# 555timers_with_allmodes.net
KiCad netlist of a schematic drawn in EAGLE
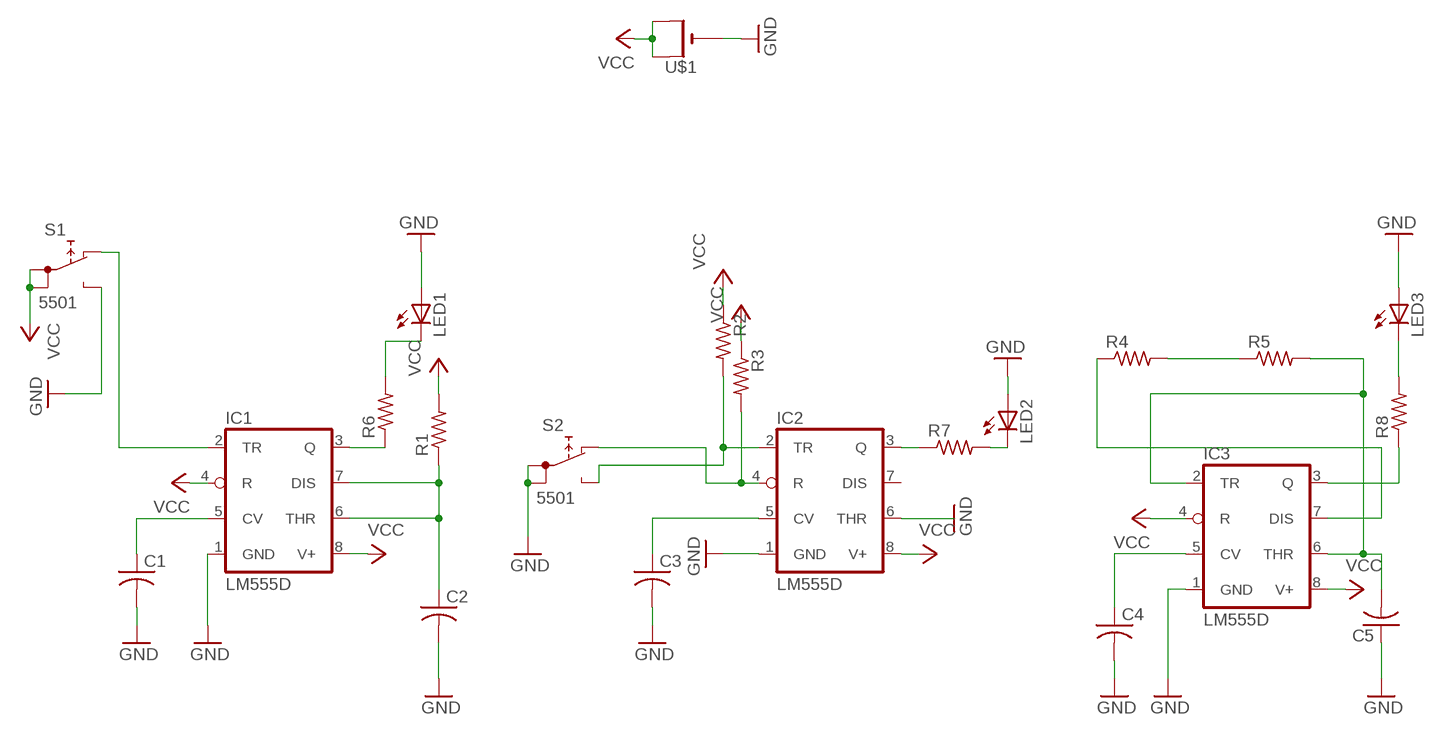
[diagram p0: schematic, sheet 1]

(export (version "E")
  (design (tool "Eeschema 10.0.6"))
  (components
    (comp (ref "C1")
      (value "C-USC0805")
      (footprint "eagle-import:C0805")
      (libsource (lib "eagle-import") (part "C-USC0805"))
    )
    (comp (ref "C2")
      (value "C-USC0805")
      (footprint "eagle-import:C0805")
      (libsource (lib "eagle-import") (part "C-USC0805"))
    )
    (comp (ref "C3")
      (value "C-USC0805")
      (footprint "eagle-import:C0805")
      (libsource (lib "eagle-import") (part "C-USC0805"))
    )
    (comp (ref "C4")
      (value "C-USC0805")
      (footprint "eagle-import:C0805")
      (libsource (lib "eagle-import") (part "C-USC0805"))
    )
    (comp (ref "C5")
      (value "C-USC0805")
      (footprint "eagle-import:C0805")
      (libsource (lib "eagle-import") (part "C-USC0805"))
    )
    (comp (ref "IC1")
      (value "LM555D")
      (footprint "eagle-import:SO08")
      (libsource (lib "eagle-import") (part "555DLM"))
    )
    (comp (ref "IC2")
      (value "LM555D")
      (footprint "eagle-import:SO08")
      (libsource (lib "eagle-import") (part "555DLM"))
    )
    (comp (ref "IC3")
      (value "LM555D")
      (footprint "eagle-import:SO08")
      (libsource (lib "eagle-import") (part "555DLM"))
    )
    (comp (ref "LED1")
      (value "LEDCHIPLED_0805")
      (footprint "eagle-import:CHIPLED_0805")
      (libsource (lib "eagle-import") (part "LEDCHIPLED_0805"))
    )
    (comp (ref "LED2")
      (value "LEDCHIPLED_0805")
      (footprint "eagle-import:CHIPLED_0805")
      (libsource (lib "eagle-import") (part "LEDCHIPLED_0805"))
    )
    (comp (ref "LED3")
      (value "LEDCHIPLED_0805")
      (footprint "eagle-import:CHIPLED_0805")
      (libsource (lib "eagle-import") (part "LEDCHIPLED_0805"))
    )
    (comp (ref "R1")
      (value "R-US_FLIPFLOP")
      (footprint "eagle-import:0805-THM")
      (libsource (lib "eagle-import") (part "R-US_FLIPFLOP"))
    )
    (comp (ref "R2")
      (value "R-US_FLIPFLOP")
      (footprint "eagle-import:0805-THM")
      (libsource (lib "eagle-import") (part "R-US_FLIPFLOP"))
    )
    (comp (ref "R3")
      (value "R-US_FLIPFLOP")
      (footprint "eagle-import:0805-THM")
      (libsource (lib "eagle-import") (part "R-US_FLIPFLOP"))
    )
    (comp (ref "R4")
      (value "R-US_FLIPFLOP")
      (footprint "eagle-import:0805-THM")
      (libsource (lib "eagle-import") (part "R-US_FLIPFLOP"))
    )
    (comp (ref "R5")
      (value "R-US_FLIPFLOP")
      (footprint "eagle-import:0805-THM")
      (libsource (lib "eagle-import") (part "R-US_FLIPFLOP"))
    )
    (comp (ref "R6")
      (value "R-US_FLIPFLOP")
      (footprint "eagle-import:0805-THM")
      (libsource (lib "eagle-import") (part "R-US_FLIPFLOP"))
    )
    (comp (ref "R7")
      (value "R-US_FLIPFLOP")
      (footprint "eagle-import:0805-THM")
      (libsource (lib "eagle-import") (part "R-US_FLIPFLOP"))
    )
    (comp (ref "R8")
      (value "R-US_FLIPFLOP")
      (footprint "eagle-import:0805-THM")
      (libsource (lib "eagle-import") (part "R-US_FLIPFLOP"))
    )
    (comp (ref "S1")
      (value "5501")
      (footprint "eagle-import:5501")
      (libsource (lib "eagle-import") (part "55?01"))
    )
    (comp (ref "S2")
      (value "5501")
      (footprint "eagle-import:5501")
      (libsource (lib "eagle-import") (part "55?01"))
    )
    (comp (ref "U$1")
      (value "CR1220SMT")
      (footprint "eagle-import:CR1220-SMD")
      (libsource (lib "eagle-import") (part "CR1220SMT"))
    )
  )
  (nets
    (net (code "1") (name "GND") (class "Default")
      (node (ref "C1") (pin "2") (pinfunction "2_2") (pintype "passive"))
      (node (ref "C2") (pin "2") (pinfunction "2_2") (pintype "passive"))
      (node (ref "C3") (pin "2") (pinfunction "2_2") (pintype "passive"))
      (node (ref "C4") (pin "2") (pinfunction "2_2") (pintype "passive"))
      (node (ref "C5") (pin "1") (pinfunction "1_1") (pintype "passive"))
      (node (ref "IC1") (pin "1") (pinfunction "GND_1") (pintype "power_in"))
      (node (ref "IC2") (pin "1") (pinfunction "GND_1") (pintype "power_in"))
      (node (ref "IC2") (pin "6") (pinfunction "THR_6") (pintype "input"))
      (node (ref "IC3") (pin "1") (pinfunction "GND_1") (pintype "power_in"))
      (node (ref "LED1") (pin "A") (pinfunction "A_A") (pintype "passive"))
      (node (ref "LED2") (pin "A") (pinfunction "A_A") (pintype "passive"))
      (node (ref "LED3") (pin "A") (pinfunction "A_A") (pintype "passive"))
      (node (ref "S1") (pin "NO") (pinfunction "NO_NO") (pintype "passive"))
      (node (ref "S2") (pin "1A") (pinfunction "1A_1A") (pintype "passive"))
      (node (ref "S2") (pin "1B") (pinfunction "1B_1B") (pintype "passive"))
      (node (ref "U$1") (pin "-") (pinfunction "-_-") (pintype "passive"))
    )
    (net (code "2") (name "Net-(IC1-CV)") (class "Default")
      (node (ref "C1") (pin "1") (pinfunction "1_1") (pintype "passive"))
      (node (ref "IC1") (pin "5") (pinfunction "CV_5") (pintype "input"))
    )
    (net (code "3") (name "Net-(IC1-DIS)") (class "Default")
      (node (ref "C2") (pin "1") (pinfunction "1_1") (pintype "passive"))
      (node (ref "IC1") (pin "6") (pinfunction "THR_6") (pintype "input"))
      (node (ref "IC1") (pin "7") (pinfunction "DIS_7") (pintype "input"))
      (node (ref "R1") (pin "1") (pinfunction "1_1") (pintype "passive"))
    )
    (net (code "4") (name "Net-(IC1-Q)") (class "Default")
      (node (ref "IC1") (pin "3") (pinfunction "Q_3") (pintype "output"))
      (node (ref "R6") (pin "1") (pinfunction "1_1") (pintype "passive"))
    )
    (net (code "5") (name "Net-(IC1-TR)") (class "Default")
      (node (ref "IC1") (pin "2") (pinfunction "TR_2") (pintype "input"))
      (node (ref "S1") (pin "NC") (pinfunction "NC_NC") (pintype "passive"))
    )
    (net (code "6") (name "Net-(IC2-CV)") (class "Default")
      (node (ref "C3") (pin "1") (pinfunction "1_1") (pintype "passive"))
      (node (ref "IC2") (pin "5") (pinfunction "CV_5") (pintype "input"))
    )
    (net (code "7") (name "Net-(IC2-Q)") (class "Default")
      (node (ref "IC2") (pin "3") (pinfunction "Q_3") (pintype "output"))
      (node (ref "R7") (pin "1") (pinfunction "1_1") (pintype "passive"))
    )
    (net (code "8") (name "Net-(IC2-R)") (class "Default")
      (node (ref "IC2") (pin "4") (pinfunction "R_4") (pintype "input"))
      (node (ref "R3") (pin "2") (pinfunction "2_2") (pintype "passive"))
      (node (ref "S2") (pin "NC") (pinfunction "NC_NC") (pintype "passive"))
    )
    (net (code "9") (name "Net-(IC2-TR)") (class "Default")
      (node (ref "IC2") (pin "2") (pinfunction "TR_2") (pintype "input"))
      (node (ref "R2") (pin "2") (pinfunction "2_2") (pintype "passive"))
      (node (ref "S2") (pin "NO") (pinfunction "NO_NO") (pintype "passive"))
    )
    (net (code "10") (name "Net-(IC3-CV)") (class "Default")
      (node (ref "C4") (pin "1") (pinfunction "1_1") (pintype "passive"))
      (node (ref "IC3") (pin "5") (pinfunction "CV_5") (pintype "input"))
    )
    (net (code "11") (name "Net-(IC3-DIS)") (class "Default")
      (node (ref "IC3") (pin "7") (pinfunction "DIS_7") (pintype "input"))
      (node (ref "R4") (pin "1") (pinfunction "1_1") (pintype "passive"))
    )
    (net (code "12") (name "Net-(IC3-Q)") (class "Default")
      (node (ref "IC3") (pin "3") (pinfunction "Q_3") (pintype "output"))
      (node (ref "R8") (pin "1") (pinfunction "1_1") (pintype "passive"))
    )
    (net (code "13") (name "Net-(IC3-THR)") (class "Default")
      (node (ref "C5") (pin "2") (pinfunction "2_2") (pintype "passive"))
      (node (ref "IC3") (pin "2") (pinfunction "TR_2") (pintype "input"))
      (node (ref "IC3") (pin "6") (pinfunction "THR_6") (pintype "input"))
      (node (ref "R5") (pin "2") (pinfunction "2_2") (pintype "passive"))
    )
    (net (code "14") (name "Net-(LED1-PadC)") (class "Default")
      (node (ref "LED1") (pin "C") (pinfunction "C_C") (pintype "passive"))
      (node (ref "R6") (pin "2") (pinfunction "2_2") (pintype "passive"))
    )
    (net (code "15") (name "Net-(LED2-PadC)") (class "Default")
      (node (ref "LED2") (pin "C") (pinfunction "C_C") (pintype "passive"))
      (node (ref "R7") (pin "2") (pinfunction "2_2") (pintype "passive"))
    )
    (net (code "16") (name "Net-(LED3-PadC)") (class "Default")
      (node (ref "LED3") (pin "C") (pinfunction "C_C") (pintype "passive"))
      (node (ref "R8") (pin "2") (pinfunction "2_2") (pintype "passive"))
    )
    (net (code "17") (name "Net-(R4-Pad2)") (class "Default")
      (node (ref "R4") (pin "2") (pinfunction "2_2") (pintype "passive"))
      (node (ref "R5") (pin "1") (pinfunction "1_1") (pintype "passive"))
    )
    (net (code "18") (name "VCC") (class "Default")
      (node (ref "IC1") (pin "4") (pinfunction "R_4") (pintype "input"))
      (node (ref "IC1") (pin "8") (pinfunction "V+_8") (pintype "power_in"))
      (node (ref "IC2") (pin "8") (pinfunction "V+_8") (pintype "power_in"))
      (node (ref "IC3") (pin "4") (pinfunction "R_4") (pintype "input"))
      (node (ref "IC3") (pin "8") (pinfunction "V+_8") (pintype "power_in"))
      (node (ref "R1") (pin "2") (pinfunction "2_2") (pintype "passive"))
      (node (ref "R2") (pin "1") (pinfunction "1_1") (pintype "passive"))
      (node (ref "R3") (pin "1") (pinfunction "1_1") (pintype "passive"))
      (node (ref "S1") (pin "1A") (pinfunction "1A_1A") (pintype "passive"))
      (node (ref "S1") (pin "1B") (pinfunction "1B_1B") (pintype "passive"))
      (node (ref "U$1") (pin "+$1") (pinfunction "+_+$1") (pintype "passive"))
      (node (ref "U$1") (pin "+$2") (pinfunction "+1_+$2") (pintype "passive"))
    )
    (net (code "19") (name "unconnected-(IC2-DIS-Pad7)") (class "Default")
      (node (ref "IC2") (pin "7") (pinfunction "DIS_7") (pintype "input"))
    )
  )
)
